# ZOWI_Main_Board_Battery_Charger.net
KiCad netlist of a schematic drawn in Altium Designer
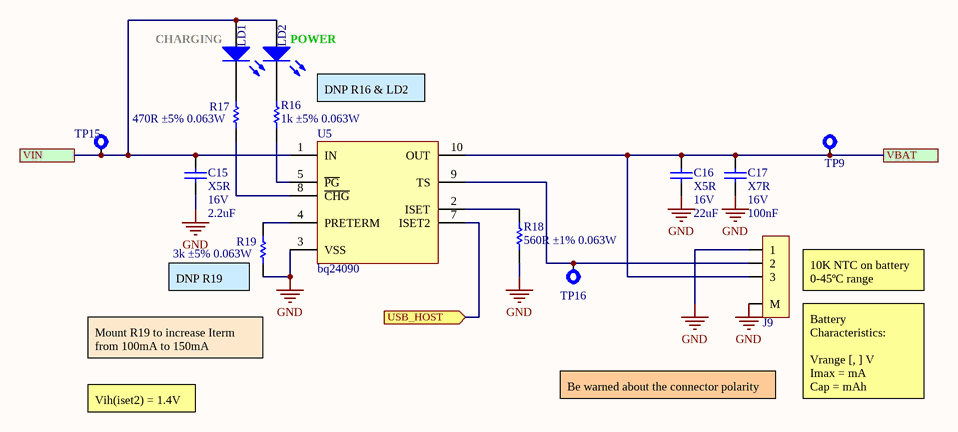
[diagram p0: ZOWI_Main_Board_Battery_Charger.SchDoc]

(export (version "E")
  (design (tool "Eeschema 10.0.6"))
  (components
    (comp (ref "C15")
      (value "Capacitor")
      (footprint "C0603")
      (description "Capacitor SMD")
      (fields
        (field (name "DIELECTRIC") "X5R")
        (field (name "VOLTAGE") "16V")
        (field (name "CAPACITANCE") "2.2uF")
        (field (name "PART NUMBER") "C0603_2.2uF_16V_±10%")
        (field (name "TOLERANCE") "±10%")
      )
      (libsource (lib "Pasives_Capacitor_SMD") (part "Capacitor"))
    )
    (comp (ref "C16")
      (value "Capacitor")
      (footprint "C0805")
      (description "Capacitor SMD")
      (fields
        (field (name "DIELECTRIC") "X5R")
        (field (name "VOLTAGE") "16V")
        (field (name "CAPACITANCE") "22uF")
        (field (name "PART NUMBER") "C0805_22uF_16V_±20%")
        (field (name "TOLERANCE") "±20%")
      )
      (libsource (lib "Pasives_Capacitor_SMD") (part "Capacitor"))
    )
    (comp (ref "C17")
      (value "Capacitor")
      (footprint "C0402")
      (description "Capacitor SMD")
      (fields
        (field (name "DIELECTRIC") "X7R")
        (field (name "VOLTAGE") "16V")
        (field (name "CAPACITANCE") "100nF")
        (field (name "PART NUMBER") "C0402_100nF_16V_±10%")
        (field (name "TOLERANCE") "±10%")
      )
      (libsource (lib "Pasives_Capacitor_SMD") (part "Capacitor"))
    )
    (comp (ref "J9")
      (value "S3B-PH-SM4-TB")
      (footprint "S3B-PH-SM4-TB")
      (description "1x3 PH connector")
      (fields (field (name "PART NUMBER") "1x3 S3B-PH-SM4-TB") (field (name "MANUFACTURER") "JST"))
      (libsource (lib "Connectors_JST") (part "S3B-XH-SM4-TB"))
    )
    (comp (ref "LD1")
      (value "Red")
      (footprint "LED_SMD_RA")
      (description "LED")
      (fields (field (name "PART NUMBER") "LED RED RIGHT ANGLE") (field (name "MANUFACTURER") "KingBright"))
      (libsource (lib "Optoelectronics") (part "LED"))
    )
    (comp (ref "LD2")
      (value "Green")
      (footprint "LED0603")
      (description "LED")
      (fields (field (name "PART NUMBER") "HSMG-C190") (field (name "MANUFACTURER") "Avago Technologies"))
      (libsource (lib "Optoelectronics") (part "LED"))
    )
    (comp (ref "R16")
      (value "1k ±5% 0.063W")
      (footprint "R0402")
      (description "Resistor, SMD")
      (fields (field (name "TOLERANCE") "±5%") (field (name "POWER") "0.063W"))
      (libsource (lib "Pasives_Resistor_SMD") (part "Resistor"))
    )
    (comp (ref "R17")
      (value "470R ±5% 0.063W")
      (footprint "R0402")
      (description "Resistor, SMD")
      (fields (field (name "TOLERANCE") "±5%") (field (name "POWER") "0.063W"))
      (libsource (lib "Pasives_Resistor_SMD") (part "Resistor"))
    )
    (comp (ref "R18")
      (value "560R ±1% 0.063W")
      (footprint "R0402")
      (description "Resistor, SMD")
      (fields (field (name "TOLERANCE") "±1%") (field (name "POWER") "0.063W"))
      (libsource (lib "Pasives_Resistor_SMD") (part "Resistor"))
    )
    (comp (ref "R19")
      (value "3k ±5% 0.063W")
      (footprint "R0402")
      (description "Resistor, SMD")
      (fields (field (name "TOLERANCE") "±5%") (field (name "POWER") "0.063W"))
      (libsource (lib "Pasives_Resistor_SMD") (part "Resistor"))
    )
    (comp (ref "TP9")
      (value "Testpoint")
      (footprint "TP_SMD_1mm")
      (fields (field (name "MANUFACTURER") "Oxley") (field (name "PART NUMBER") "TP_SMD_1mm"))
      (libsource (lib "Miscelanea") (part "Testpoint"))
    )
    (comp (ref "TP15")
      (value "Testpoint")
      (footprint "TP_SMD_1mm")
      (fields (field (name "MANUFACTURER") "Oxley") (field (name "PART NUMBER") "TP_SMD_1mm"))
      (libsource (lib "Miscelanea") (part "Testpoint"))
    )
    (comp (ref "TP16")
      (value "Testpoint")
      (footprint "TP_SMD_1mm")
      (fields (field (name "MANUFACTURER") "Oxley") (field (name "PART NUMBER") "TP_SMD_1mm"))
      (libsource (lib "Miscelanea") (part "Testpoint"))
    )
    (comp (ref "U5")
      (value "bq24090")
      (footprint "MSOP-10_5x3MM")
      (description "Battery Charger, Li-Po/Li-ion, Single Cell")
      (fields (field (name "MANUFACTURER") "Texas Instruments"))
      (libsource (lib "Power_Management") (part "BQ24095"))
    )
  )
  (nets
    (net (code "1") (name "/USB_HOST") (class "Default")
      (node (ref "U5") (pin "7") (pinfunction "ISET2_7") (pintype "passive"))
    )
    (net (code "2") (name "/VBAT") (class "Default")
      (node (ref "C16") (pin "2") (pinfunction "2_2") (pintype "passive"))
      (node (ref "C17") (pin "2") (pinfunction "2_2") (pintype "passive"))
      (node (ref "J9") (pin "3") (pinfunction "3_3") (pintype "power_in"))
      (node (ref "TP9") (pin "1") (pinfunction "1_1") (pintype "passive"))
      (node (ref "U5") (pin "10") (pinfunction "OUT_10") (pintype "passive"))
    )
    (net (code "3") (name "/VIN") (class "Default")
      (node (ref "C15") (pin "2") (pinfunction "2_2") (pintype "passive"))
      (node (ref "LD1") (pin "A") (pinfunction "A_A") (pintype "passive"))
      (node (ref "LD2") (pin "A") (pinfunction "A_A") (pintype "passive"))
      (node (ref "TP15") (pin "1") (pinfunction "1_1") (pintype "passive"))
      (node (ref "U5") (pin "1") (pinfunction "IN_1") (pintype "power_in"))
    )
    (net (code "4") (name "GND") (class "Default")
      (node (ref "C15") (pin "1") (pinfunction "1_1") (pintype "passive"))
      (node (ref "C16") (pin "1") (pinfunction "1_1") (pintype "passive"))
      (node (ref "C17") (pin "1") (pinfunction "1_1") (pintype "passive"))
      (node (ref "J9") (pin "1") (pinfunction "1_1") (pintype "power_in"))
      (node (ref "J9") (pin "M") (pinfunction "M_M") (pintype "passive"))
      (node (ref "R18") (pin "1") (pinfunction "1_1") (pintype "passive"))
      (node (ref "R19") (pin "1") (pinfunction "1_1") (pintype "passive"))
      (node (ref "U5") (pin "3") (pinfunction "VSS_3") (pintype "power_in"))
    )
    (net (code "5") (name "Net-(LD1-PadK)") (class "Default")
      (node (ref "LD1") (pin "K") (pinfunction "K_K") (pintype "passive"))
      (node (ref "R17") (pin "2") (pinfunction "2_2") (pintype "passive"))
    )
    (net (code "6") (name "Net-(LD2-PadK)") (class "Default")
      (node (ref "LD2") (pin "K") (pinfunction "K_K") (pintype "passive"))
      (node (ref "R16") (pin "2") (pinfunction "2_2") (pintype "passive"))
    )
    (net (code "7") (name "Net-(U5-ISET)") (class "Default")
      (node (ref "R18") (pin "2") (pinfunction "2_2") (pintype "passive"))
      (node (ref "U5") (pin "2") (pinfunction "ISET_2") (pintype "passive"))
    )
    (net (code "8") (name "Net-(U5-PRETERM)") (class "Default")
      (node (ref "R19") (pin "2") (pinfunction "2_2") (pintype "passive"))
      (node (ref "U5") (pin "4") (pinfunction "PRETERM_4") (pintype "power_in"))
    )
    (net (code "9") (name "Net-(U5-TS)") (class "Default")
      (node (ref "J9") (pin "2") (pinfunction "2_2") (pintype "power_in"))
      (node (ref "TP16") (pin "1") (pinfunction "1_1") (pintype "passive"))
      (node (ref "U5") (pin "9") (pinfunction "TS_9") (pintype "passive"))
    )
    (net (code "10") (name "Net-(U5-~{CHG})") (class "Default")
      (node (ref "R17") (pin "1") (pinfunction "1_1") (pintype "passive"))
      (node (ref "U5") (pin "8") (pinfunction "~{CHG}_8") (pintype "passive"))
    )
    (net (code "11") (name "Net-(U5-~{PG})") (class "Default")
      (node (ref "R16") (pin "1") (pinfunction "1_1") (pintype "passive"))
      (node (ref "U5") (pin "5") (pinfunction "~{PG}_5") (pintype "passive"))
    )
  )
)
